# SCH_PresenceIndicator_2021-10-22.net
KiCad netlist of a schematic drawn in EasyEDA
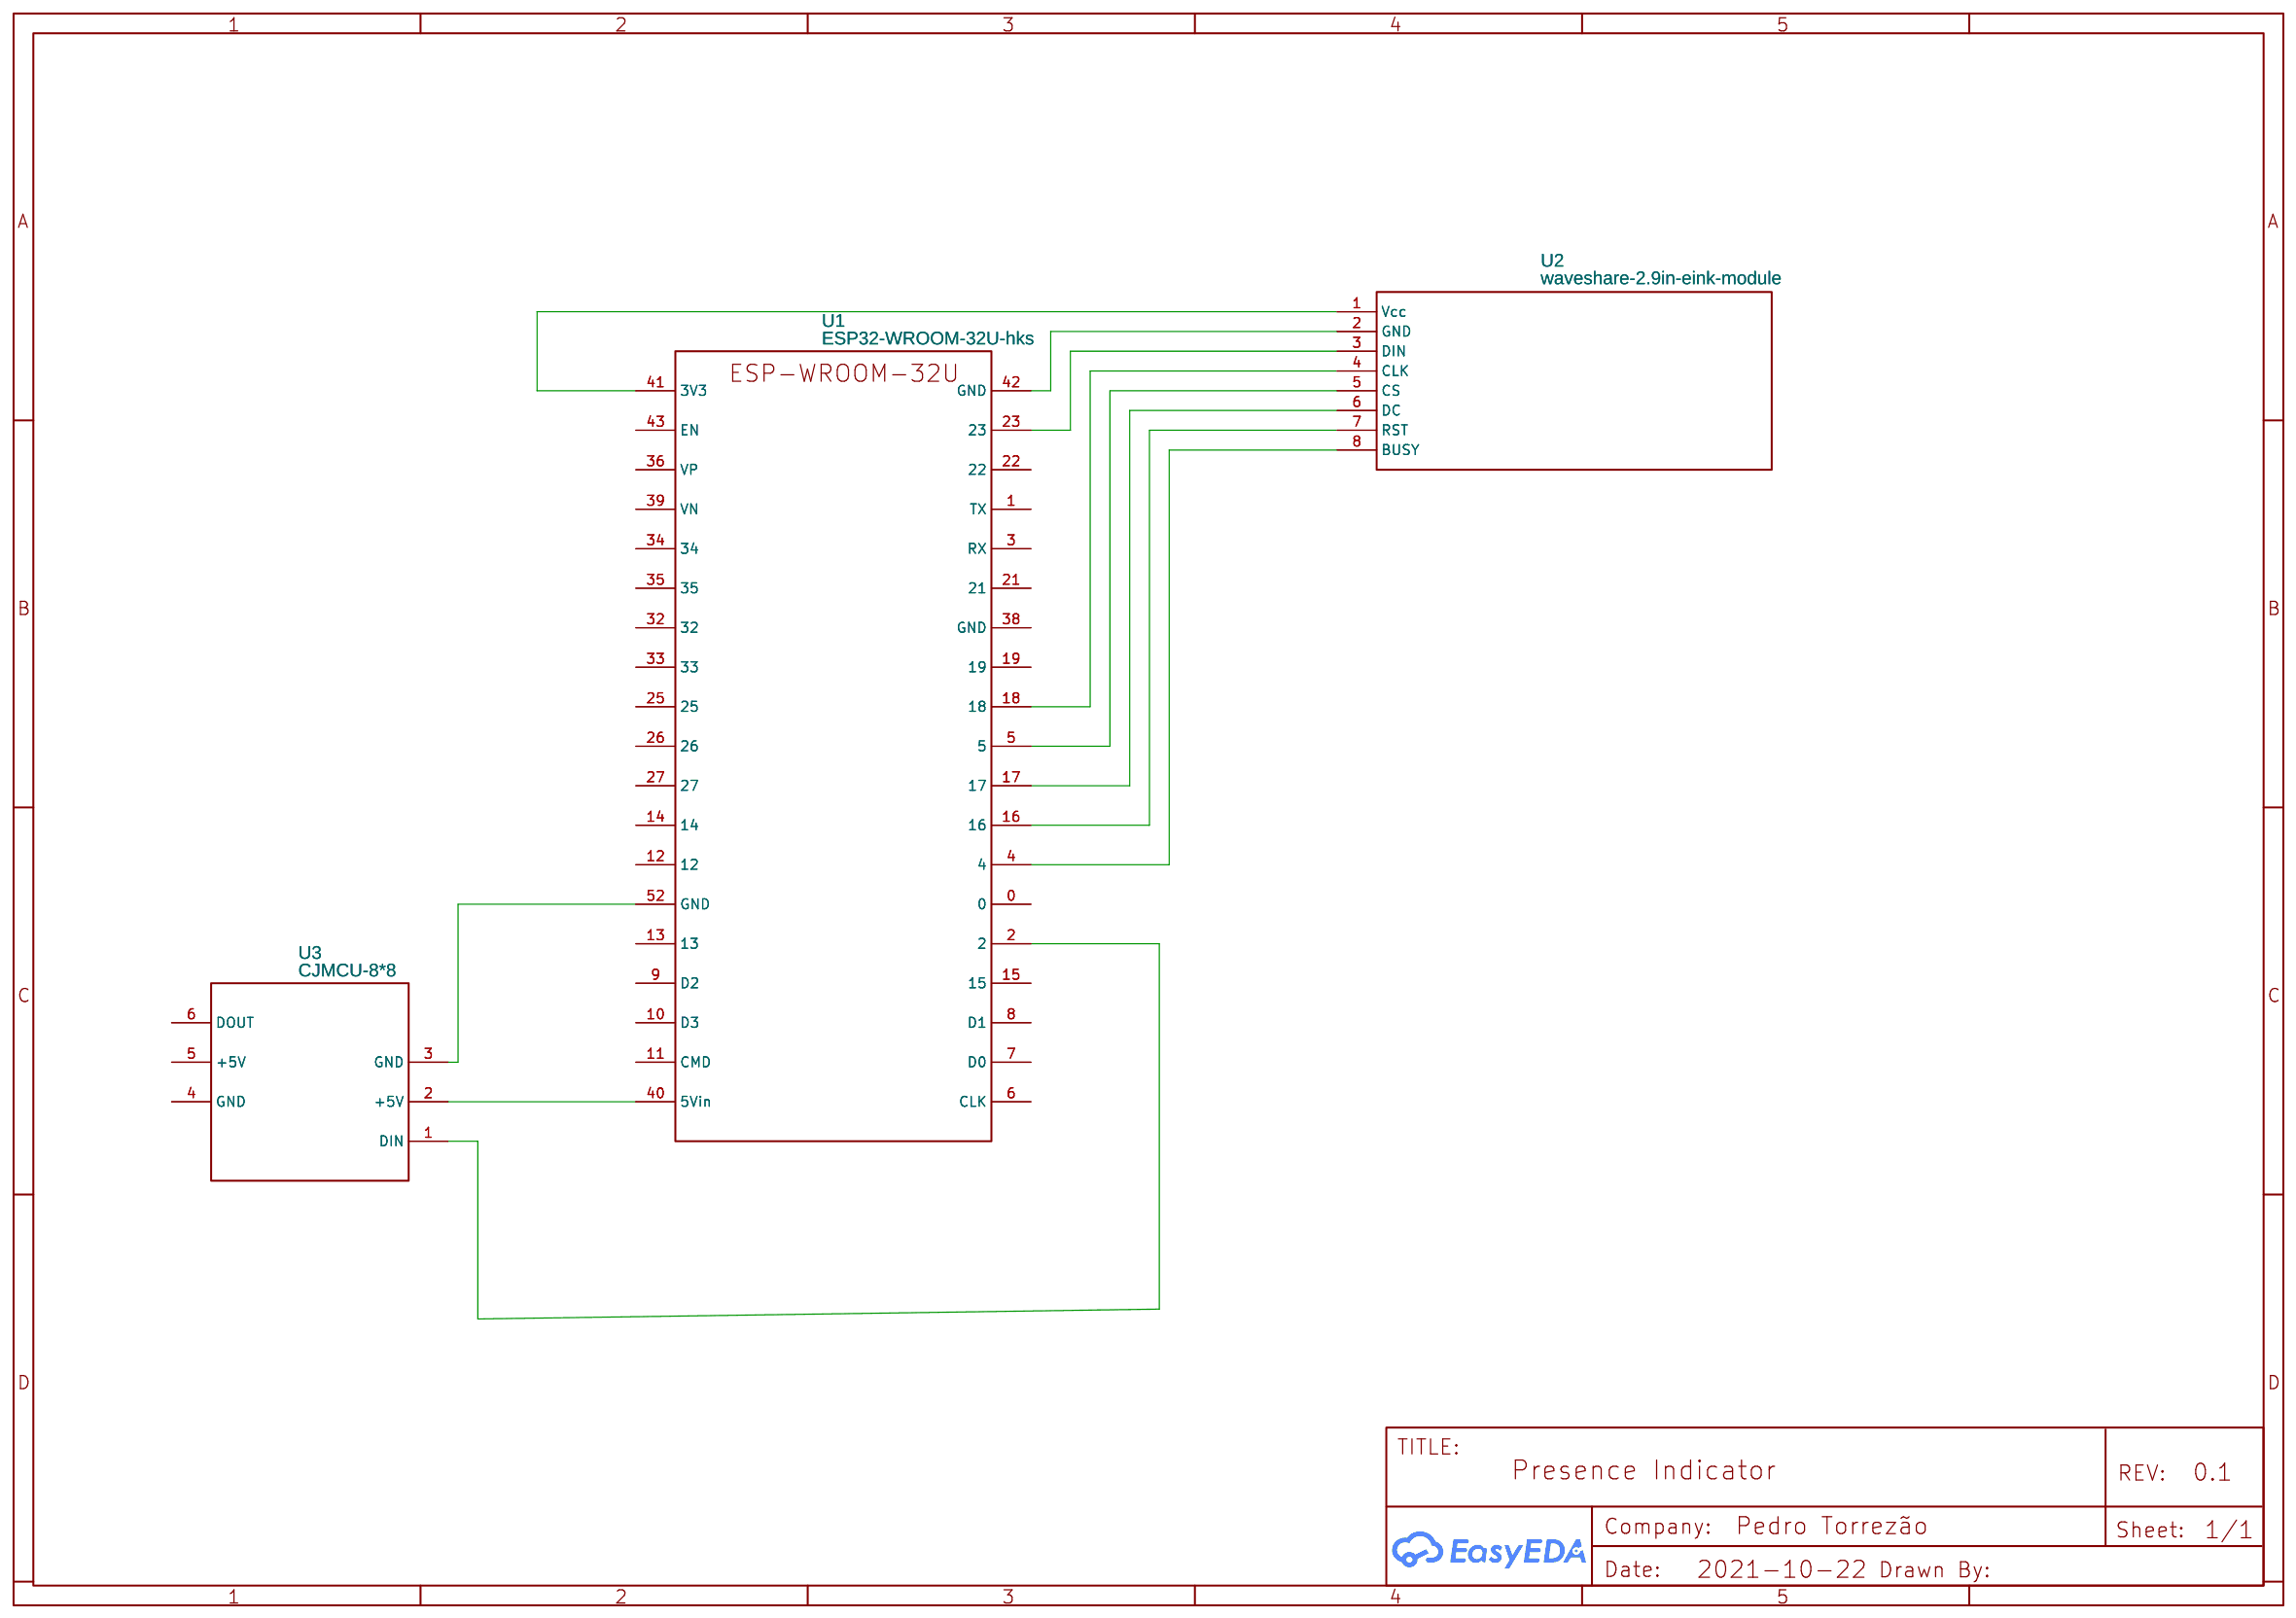
[diagram p0: schematic sheet]

(export (version "E")
  (design (tool "Eeschema 10.0.6"))
  (components
    (comp (ref "U1")
      (value "ESP32-WROOM-32U-hks")
      (fields
        (field (name "BOM_Manufacturer Part") "ESP32-DevKitC")
        (field (name "BOM_Supplier Part") "356-ESP32-DEVKITC")
      )
      (libsource (lib "") (part "ESP32-WROOM-32U-hks"))
    )
    (comp (ref "U2")
      (value "waveshare-2.9in-eink-module")
      (fields (field (name "BOM_Manufacturer Part") "2.9inch e-Paper Module (B)"))
      (libsource (lib "") (part "waveshare-2.9in-eink-module"))
    )
    (comp (ref "U3") (value "CJMCU-8*8") (libsource (lib "") (part "CJMCU-8*8")))
  )
  (nets
    (net (code "1") (name "Net-(U1-3V3)") (class "Default")
      (node (ref "U1") (pin "41") (pinfunction "3V3_41") (pintype "unspecified"))
      (node (ref "U2") (pin "1") (pinfunction "Vcc_1") (pintype "unspecified"))
    )
    (net (code "2") (name "Net-(U1-5Vin)") (class "Default")
      (node (ref "U1") (pin "40") (pinfunction "5Vin_40") (pintype "unspecified"))
      (node (ref "U3") (pin "2") (pinfunction "+5V_2") (pintype "unspecified"))
    )
    (net (code "3") (name "Net-(U1-GND-Pad52)") (class "Default")
      (node (ref "U1") (pin "52") (pinfunction "GND_52") (pintype "unspecified"))
      (node (ref "U3") (pin "3") (pinfunction "GND_3") (pintype "unspecified"))
    )
    (net (code "4") (name "Net-(U2-BUSY)") (class "Default")
      (node (ref "U1") (pin "4") (pinfunction "4_4") (pintype "unspecified"))
      (node (ref "U2") (pin "8") (pinfunction "BUSY_8") (pintype "unspecified"))
    )
    (net (code "5") (name "Net-(U2-CLK)") (class "Default")
      (node (ref "U1") (pin "18") (pinfunction "18_18") (pintype "unspecified"))
      (node (ref "U2") (pin "4") (pinfunction "CLK_4") (pintype "unspecified"))
    )
    (net (code "6") (name "Net-(U2-CS)") (class "Default")
      (node (ref "U1") (pin "5") (pinfunction "5_5") (pintype "unspecified"))
      (node (ref "U2") (pin "5") (pinfunction "CS_5") (pintype "unspecified"))
    )
    (net (code "7") (name "Net-(U2-DC)") (class "Default")
      (node (ref "U1") (pin "17") (pinfunction "17_17") (pintype "unspecified"))
      (node (ref "U2") (pin "6") (pinfunction "DC_6") (pintype "unspecified"))
    )
    (net (code "8") (name "Net-(U2-DIN)") (class "Default")
      (node (ref "U1") (pin "23") (pinfunction "23_23") (pintype "unspecified"))
      (node (ref "U2") (pin "3") (pinfunction "DIN_3") (pintype "unspecified"))
    )
    (net (code "9") (name "Net-(U2-GND)") (class "Default")
      (node (ref "U1") (pin "42") (pinfunction "GND_42") (pintype "unspecified"))
      (node (ref "U2") (pin "2") (pinfunction "GND_2") (pintype "unspecified"))
    )
    (net (code "10") (name "Net-(U2-RST)") (class "Default")
      (node (ref "U1") (pin "16") (pinfunction "16_16") (pintype "unspecified"))
      (node (ref "U2") (pin "7") (pinfunction "RST_7") (pintype "unspecified"))
    )
    (net (code "11") (name "Net-(U3-DIN)") (class "Default")
      (node (ref "U1") (pin "2") (pinfunction "2_2") (pintype "unspecified"))
      (node (ref "U3") (pin "1") (pinfunction "DIN_1") (pintype "unspecified"))
    )
    (net (code "12") (name "unconnected-(U1-CLK-Pad6)") (class "Default")
      (node (ref "U1") (pin "6") (pinfunction "CLK_6") (pintype "unspecified"))
    )
    (net (code "13") (name "unconnected-(U1-CMD-Pad11)") (class "Default")
      (node (ref "U1") (pin "11") (pinfunction "CMD_11") (pintype "unspecified"))
    )
    (net (code "14") (name "unconnected-(U1-D0-Pad7)") (class "Default")
      (node (ref "U1") (pin "7") (pinfunction "D0_7") (pintype "unspecified"))
    )
    (net (code "15") (name "unconnected-(U1-D1-Pad8)") (class "Default")
      (node (ref "U1") (pin "8") (pinfunction "D1_8") (pintype "unspecified"))
    )
    (net (code "16") (name "unconnected-(U1-D2-Pad9)") (class "Default")
      (node (ref "U1") (pin "9") (pinfunction "D2_9") (pintype "unspecified"))
    )
    (net (code "17") (name "unconnected-(U1-D3-Pad10)") (class "Default")
      (node (ref "U1") (pin "10") (pinfunction "D3_10") (pintype "unspecified"))
    )
    (net (code "18") (name "unconnected-(U1-EN-Pad43)") (class "Default")
      (node (ref "U1") (pin "43") (pinfunction "EN_43") (pintype "unspecified"))
    )
    (net (code "19") (name "unconnected-(U1-GND-Pad38)") (class "Default")
      (node (ref "U1") (pin "38") (pinfunction "GND_38") (pintype "unspecified"))
    )
    (net (code "20") (name "unconnected-(U1-Pad0)") (class "Default")
      (node (ref "U1") (pin "0") (pinfunction "0_0") (pintype "unspecified"))
    )
    (net (code "21") (name "unconnected-(U1-Pad12)") (class "Default")
      (node (ref "U1") (pin "12") (pinfunction "12_12") (pintype "unspecified"))
    )
    (net (code "22") (name "unconnected-(U1-Pad13)") (class "Default")
      (node (ref "U1") (pin "13") (pinfunction "13_13") (pintype "unspecified"))
    )
    (net (code "23") (name "unconnected-(U1-Pad14)") (class "Default")
      (node (ref "U1") (pin "14") (pinfunction "14_14") (pintype "unspecified"))
    )
    (net (code "24") (name "unconnected-(U1-Pad15)") (class "Default")
      (node (ref "U1") (pin "15") (pinfunction "15_15") (pintype "unspecified"))
    )
    (net (code "25") (name "unconnected-(U1-Pad19)") (class "Default")
      (node (ref "U1") (pin "19") (pinfunction "19_19") (pintype "unspecified"))
    )
    (net (code "26") (name "unconnected-(U1-Pad21)") (class "Default")
      (node (ref "U1") (pin "21") (pinfunction "21_21") (pintype "unspecified"))
    )
    (net (code "27") (name "unconnected-(U1-Pad22)") (class "Default")
      (node (ref "U1") (pin "22") (pinfunction "22_22") (pintype "unspecified"))
    )
    (net (code "28") (name "unconnected-(U1-Pad25)") (class "Default")
      (node (ref "U1") (pin "25") (pinfunction "25_25") (pintype "unspecified"))
    )
    (net (code "29") (name "unconnected-(U1-Pad26)") (class "Default")
      (node (ref "U1") (pin "26") (pinfunction "26_26") (pintype "unspecified"))
    )
    (net (code "30") (name "unconnected-(U1-Pad27)") (class "Default")
      (node (ref "U1") (pin "27") (pinfunction "27_27") (pintype "unspecified"))
    )
    (net (code "31") (name "unconnected-(U1-Pad32)") (class "Default")
      (node (ref "U1") (pin "32") (pinfunction "32_32") (pintype "unspecified"))
    )
    (net (code "32") (name "unconnected-(U1-Pad33)") (class "Default")
      (node (ref "U1") (pin "33") (pinfunction "33_33") (pintype "unspecified"))
    )
    (net (code "33") (name "unconnected-(U1-Pad34)") (class "Default")
      (node (ref "U1") (pin "34") (pinfunction "34_34") (pintype "unspecified"))
    )
    (net (code "34") (name "unconnected-(U1-Pad35)") (class "Default")
      (node (ref "U1") (pin "35") (pinfunction "35_35") (pintype "unspecified"))
    )
    (net (code "35") (name "unconnected-(U1-RX-Pad3)") (class "Default")
      (node (ref "U1") (pin "3") (pinfunction "RX_3") (pintype "unspecified"))
    )
    (net (code "36") (name "unconnected-(U1-TX-Pad1)") (class "Default")
      (node (ref "U1") (pin "1") (pinfunction "TX_1") (pintype "unspecified"))
    )
    (net (code "37") (name "unconnected-(U1-VN-Pad39)") (class "Default")
      (node (ref "U1") (pin "39") (pinfunction "VN_39") (pintype "unspecified"))
    )
    (net (code "38") (name "unconnected-(U1-VP-Pad36)") (class "Default")
      (node (ref "U1") (pin "36") (pinfunction "VP_36") (pintype "unspecified"))
    )
    (net (code "39") (name "unconnected-(U3-+5V-Pad5)") (class "Default")
      (node (ref "U3") (pin "5") (pinfunction "+5V_5") (pintype "unspecified"))
    )
    (net (code "40") (name "unconnected-(U3-DOUT-Pad6)") (class "Default")
      (node (ref "U3") (pin "6") (pinfunction "DOUT_6") (pintype "unspecified"))
    )
    (net (code "41") (name "unconnected-(U3-GND-Pad4)") (class "Default")
      (node (ref "U3") (pin "4") (pinfunction "GND_4") (pintype "unspecified"))
    )
  )
)
